# Motherboard.net
KiCad netlist of a schematic drawn in EAGLE
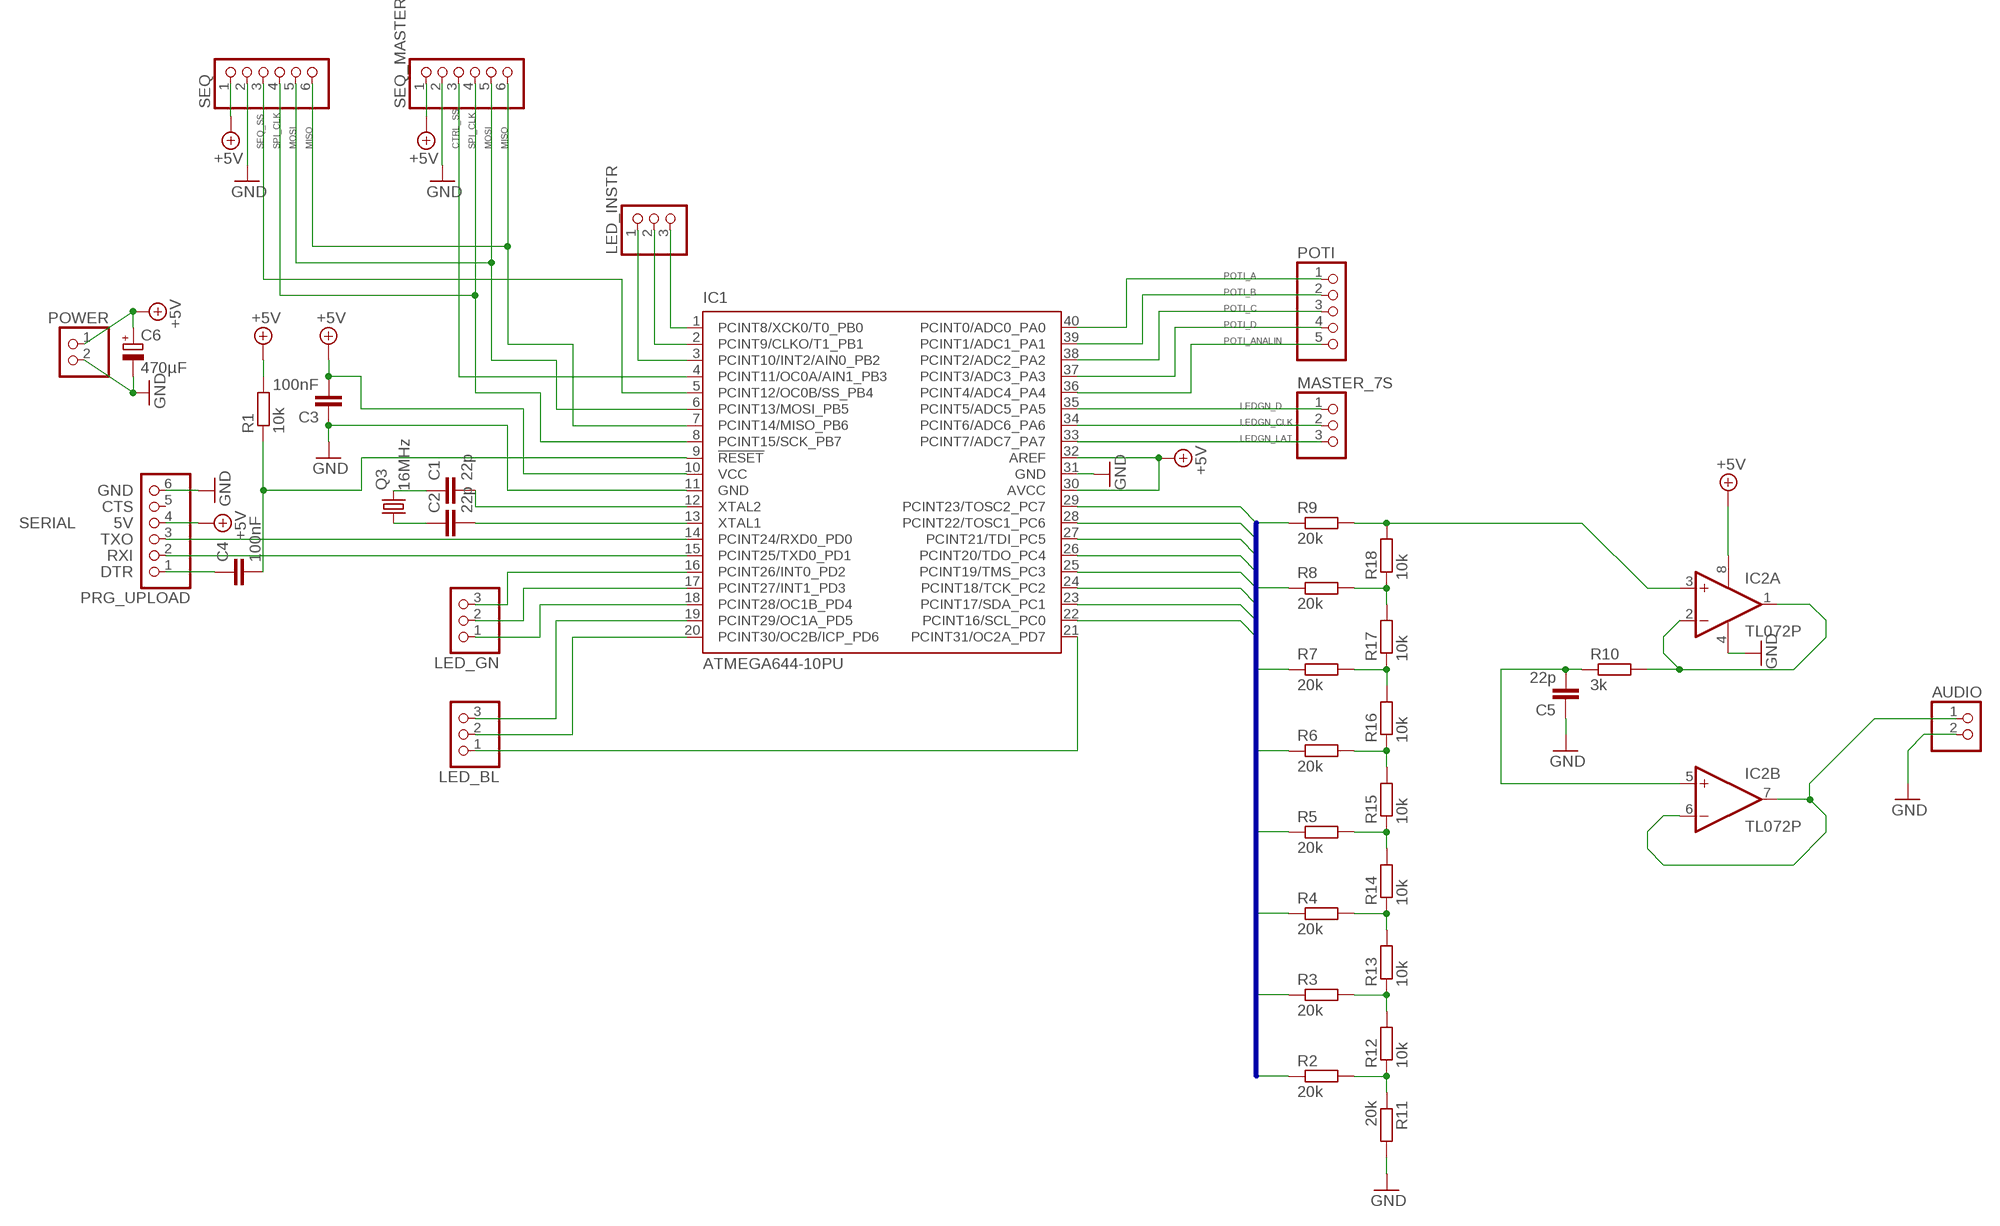
[diagram p0: schematic, sheet 1]

(export (version "E")
  (design (tool "Eeschema 10.0.6"))
  (components
    (comp (ref "AUDIO")
      (value "PINHD-1X2")
      (footprint "eagle-import:1X02")
      (libsource (lib "eagle-import") (part "PINHD-1X2"))
    )
    (comp (ref "C1")
      (value "22p")
      (footprint "eagle-import:C025-060X050")
      (libsource (lib "eagle-import") (part "C-EU025-060X050"))
    )
    (comp (ref "C2")
      (value "22p")
      (footprint "eagle-import:C025-060X050")
      (libsource (lib "eagle-import") (part "C-EU025-060X050"))
    )
    (comp (ref "C3")
      (value "100nF")
      (footprint "eagle-import:C025-060X050")
      (libsource (lib "eagle-import") (part "C-EU025-060X050"))
    )
    (comp (ref "C4")
      (value "100nF")
      (footprint "eagle-import:C025-060X050")
      (libsource (lib "eagle-import") (part "C-EU025-060X050"))
    )
    (comp (ref "C5")
      (value "22p")
      (footprint "eagle-import:C025-060X050")
      (libsource (lib "eagle-import") (part "C-EU025-060X050"))
    )
    (comp (ref "C6")
      (value "470µF")
      (footprint "eagle-import:E3,5-10")
      (libsource (lib "eagle-import") (part "CPOL-EUE3.5-10"))
    )
    (comp (ref "IC1")
      (value "ATMEGA644-10PU")
      (footprint "eagle-import:DIL40")
      (fields (field (name "MPN") "ATMEGA644V-10PU"))
      (libsource (lib "eagle-import") (part "ATMEGA644-PU10"))
    )
    (comp (ref "IC2")
      (value "TL072P")
      (footprint "eagle-import:DIL08")
      (libsource (lib "eagle-import") (part "TL072P"))
    )
    (comp (ref "LED_BL")
      (value "PINHD-1X3")
      (footprint "eagle-import:1X03")
      (libsource (lib "eagle-import") (part "PINHD-1X3"))
    )
    (comp (ref "LED_GN")
      (value "PINHD-1X3")
      (footprint "eagle-import:1X03")
      (libsource (lib "eagle-import") (part "PINHD-1X3"))
    )
    (comp (ref "LED_INSTR")
      (value "PINHD-1X3")
      (footprint "eagle-import:1X03")
      (libsource (lib "eagle-import") (part "PINHD-1X3"))
    )
    (comp (ref "MASTER_7S")
      (value "PINHD-1X3")
      (footprint "eagle-import:1X03")
      (libsource (lib "eagle-import") (part "PINHD-1X3"))
    )
    (comp (ref "POTI")
      (value "PINHD-1X5")
      (footprint "eagle-import:1X05")
      (libsource (lib "eagle-import") (part "PINHD-1X5"))
    )
    (comp (ref "POWER")
      (value "PINHD-1X2")
      (footprint "eagle-import:1X02")
      (libsource (lib "eagle-import") (part "PINHD-1X2"))
    )
    (comp (ref "PRG_UPLOAD")
      (value "PINHD-1X6")
      (footprint "eagle-import:1X06")
      (libsource (lib "eagle-import") (part "PINHD-1X6"))
    )
    (comp (ref "Q3")
      (value "16MHz")
      (footprint "eagle-import:HC18U-V")
      (libsource (lib "eagle-import") (part "CRYSTALHC18U-V"))
    )
    (comp (ref "R1")
      (value "10k")
      (footprint "eagle-import:0204_7")
      (libsource (lib "eagle-import") (part "R-EU_0204/7"))
    )
    (comp (ref "R2")
      (value "20k")
      (footprint "eagle-import:0204_7")
      (libsource (lib "eagle-import") (part "R-EU_0204/7"))
    )
    (comp (ref "R3")
      (value "20k")
      (footprint "eagle-import:0204_7")
      (libsource (lib "eagle-import") (part "R-EU_0204/7"))
    )
    (comp (ref "R4")
      (value "20k")
      (footprint "eagle-import:0204_7")
      (libsource (lib "eagle-import") (part "R-EU_0204/7"))
    )
    (comp (ref "R5")
      (value "20k")
      (footprint "eagle-import:0204_7")
      (libsource (lib "eagle-import") (part "R-EU_0204/7"))
    )
    (comp (ref "R6")
      (value "20k")
      (footprint "eagle-import:0204_7")
      (libsource (lib "eagle-import") (part "R-EU_0204/7"))
    )
    (comp (ref "R7")
      (value "20k")
      (footprint "eagle-import:0204_7")
      (libsource (lib "eagle-import") (part "R-EU_0204/7"))
    )
    (comp (ref "R8")
      (value "20k")
      (footprint "eagle-import:0204_7")
      (libsource (lib "eagle-import") (part "R-EU_0204/7"))
    )
    (comp (ref "R9")
      (value "20k")
      (footprint "eagle-import:0204_7")
      (libsource (lib "eagle-import") (part "R-EU_0204/7"))
    )
    (comp (ref "R10")
      (value "3k")
      (footprint "eagle-import:0204_7")
      (libsource (lib "eagle-import") (part "R-EU_0204/7"))
    )
    (comp (ref "R11")
      (value "20k")
      (footprint "eagle-import:0204_7")
      (libsource (lib "eagle-import") (part "R-EU_0204/7"))
    )
    (comp (ref "R12")
      (value "10k")
      (footprint "eagle-import:0204_7")
      (libsource (lib "eagle-import") (part "R-EU_0204/7"))
    )
    (comp (ref "R13")
      (value "10k")
      (footprint "eagle-import:0204_7")
      (libsource (lib "eagle-import") (part "R-EU_0204/7"))
    )
    (comp (ref "R14")
      (value "10k")
      (footprint "eagle-import:0204_7")
      (libsource (lib "eagle-import") (part "R-EU_0204/7"))
    )
    (comp (ref "R15")
      (value "10k")
      (footprint "eagle-import:0204_7")
      (libsource (lib "eagle-import") (part "R-EU_0204/7"))
    )
    (comp (ref "R16")
      (value "10k")
      (footprint "eagle-import:0204_7")
      (libsource (lib "eagle-import") (part "R-EU_0204/7"))
    )
    (comp (ref "R17")
      (value "10k")
      (footprint "eagle-import:0204_7")
      (libsource (lib "eagle-import") (part "R-EU_0204/7"))
    )
    (comp (ref "R18")
      (value "10k")
      (footprint "eagle-import:0204_7")
      (libsource (lib "eagle-import") (part "R-EU_0204/7"))
    )
    (comp (ref "SEQ")
      (value "PINHD-1X6")
      (footprint "eagle-import:1X06")
      (libsource (lib "eagle-import") (part "PINHD-1X6"))
    )
    (comp (ref "SEQ_MASTER")
      (value "PINHD-1X6")
      (footprint "eagle-import:1X06")
      (libsource (lib "eagle-import") (part "PINHD-1X6"))
    )
  )
  (nets
    (net (code "1") (name "+5V") (class "Default")
      (node (ref "C3") (pin "2") (pinfunction "2_2") (pintype "passive"))
      (node (ref "C6") (pin "+") (pinfunction "+_+") (pintype "passive"))
      (node (ref "IC1") (pin "10") (pinfunction "VCC_10") (pintype "power_in"))
      (node (ref "IC1") (pin "30") (pinfunction "AVCC_30") (pintype "power_in"))
      (node (ref "IC1") (pin "32") (pinfunction "AREF_32") (pintype "passive"))
      (node (ref "IC2") (pin "8") (pinfunction "V+_8") (pintype "power_in"))
      (node (ref "POWER") (pin "1") (pinfunction "1_1") (pintype "passive"))
      (node (ref "PRG_UPLOAD") (pin "4") (pinfunction "4_4") (pintype "passive"))
      (node (ref "R1") (pin "2") (pinfunction "2_2") (pintype "passive"))
      (node (ref "SEQ") (pin "1") (pinfunction "1_1") (pintype "passive"))
      (node (ref "SEQ_MASTER") (pin "1") (pinfunction "1_1") (pintype "passive"))
    )
    (net (code "2") (name "/CTRL_SS") (class "Default")
      (node (ref "IC1") (pin "4") (pinfunction "PCINT11/OC0A/AIN1_PB3_4") (pintype "bidirectional"))
      (node (ref "SEQ_MASTER") (pin "3") (pinfunction "3_3") (pintype "passive"))
    )
    (net (code "3") (name "/DA0") (class "Default")
      (node (ref "IC1") (pin "22") (pinfunction "PCINT16/SCL_PC0_22") (pintype "bidirectional"))
      (node (ref "R2") (pin "1") (pinfunction "1_1") (pintype "passive"))
    )
    (net (code "4") (name "/DA1") (class "Default")
      (node (ref "IC1") (pin "23") (pinfunction "PCINT17/SDA_PC1_23") (pintype "bidirectional"))
      (node (ref "R3") (pin "1") (pinfunction "1_1") (pintype "passive"))
    )
    (net (code "5") (name "/DA2") (class "Default")
      (node (ref "IC1") (pin "24") (pinfunction "PCINT18/TCK_PC2_24") (pintype "bidirectional"))
      (node (ref "R4") (pin "1") (pinfunction "1_1") (pintype "passive"))
    )
    (net (code "6") (name "/DA3") (class "Default")
      (node (ref "IC1") (pin "25") (pinfunction "PCINT19/TMS_PC3_25") (pintype "bidirectional"))
      (node (ref "R5") (pin "1") (pinfunction "1_1") (pintype "passive"))
    )
    (net (code "7") (name "/DA4") (class "Default")
      (node (ref "IC1") (pin "26") (pinfunction "PCINT20/TDO_PC4_26") (pintype "bidirectional"))
      (node (ref "R6") (pin "1") (pinfunction "1_1") (pintype "passive"))
    )
    (net (code "8") (name "/DA5") (class "Default")
      (node (ref "IC1") (pin "27") (pinfunction "PCINT21/TDI_PC5_27") (pintype "bidirectional"))
      (node (ref "R7") (pin "1") (pinfunction "1_1") (pintype "passive"))
    )
    (net (code "9") (name "/DA6") (class "Default")
      (node (ref "IC1") (pin "28") (pinfunction "PCINT22/TOSC1_PC6_28") (pintype "bidirectional"))
      (node (ref "R8") (pin "1") (pinfunction "1_1") (pintype "passive"))
    )
    (net (code "10") (name "/DA7") (class "Default")
      (node (ref "IC1") (pin "29") (pinfunction "PCINT23/TOSC2_PC7_29") (pintype "bidirectional"))
      (node (ref "R9") (pin "1") (pinfunction "1_1") (pintype "passive"))
    )
    (net (code "11") (name "/LEDGN_CLK") (class "Default")
      (node (ref "IC1") (pin "34") (pinfunction "PCINT6/ADC6_PA6_34") (pintype "bidirectional"))
      (node (ref "MASTER_7S") (pin "2") (pinfunction "2_2") (pintype "passive"))
    )
    (net (code "12") (name "/LEDGN_D") (class "Default")
      (node (ref "IC1") (pin "35") (pinfunction "PCINT5/ADC5_PA5_35") (pintype "bidirectional"))
      (node (ref "MASTER_7S") (pin "1") (pinfunction "1_1") (pintype "passive"))
    )
    (net (code "13") (name "/LEDGN_LAT") (class "Default")
      (node (ref "IC1") (pin "33") (pinfunction "PCINT7/ADC7_PA7_33") (pintype "bidirectional"))
      (node (ref "MASTER_7S") (pin "3") (pinfunction "3_3") (pintype "passive"))
    )
    (net (code "14") (name "/MISO") (class "Default")
      (node (ref "IC1") (pin "7") (pinfunction "PCINT14/MISO_PB6_7") (pintype "bidirectional"))
      (node (ref "SEQ") (pin "6") (pinfunction "6_6") (pintype "passive"))
      (node (ref "SEQ_MASTER") (pin "6") (pinfunction "6_6") (pintype "passive"))
    )
    (net (code "15") (name "/MOSI") (class "Default")
      (node (ref "IC1") (pin "6") (pinfunction "PCINT13/MOSI_PB5_6") (pintype "bidirectional"))
      (node (ref "SEQ") (pin "5") (pinfunction "5_5") (pintype "passive"))
      (node (ref "SEQ_MASTER") (pin "5") (pinfunction "5_5") (pintype "passive"))
    )
    (net (code "16") (name "/POTI_A") (class "Default")
      (node (ref "IC1") (pin "40") (pinfunction "PCINT0/ADC0_PA0_40") (pintype "bidirectional"))
      (node (ref "POTI") (pin "1") (pinfunction "1_1") (pintype "passive"))
    )
    (net (code "17") (name "/POTI_ANALIN") (class "Default")
      (node (ref "IC1") (pin "36") (pinfunction "PCINT4/ADC4_PA4_36") (pintype "bidirectional"))
      (node (ref "POTI") (pin "5") (pinfunction "5_5") (pintype "passive"))
    )
    (net (code "18") (name "/POTI_B") (class "Default")
      (node (ref "IC1") (pin "39") (pinfunction "PCINT1/ADC1_PA1_39") (pintype "bidirectional"))
      (node (ref "POTI") (pin "2") (pinfunction "2_2") (pintype "passive"))
    )
    (net (code "19") (name "/POTI_C") (class "Default")
      (node (ref "IC1") (pin "38") (pinfunction "PCINT2/ADC2_PA2_38") (pintype "bidirectional"))
      (node (ref "POTI") (pin "3") (pinfunction "3_3") (pintype "passive"))
    )
    (net (code "20") (name "/POTI_D") (class "Default")
      (node (ref "IC1") (pin "37") (pinfunction "PCINT3/ADC3_PA3_37") (pintype "bidirectional"))
      (node (ref "POTI") (pin "4") (pinfunction "4_4") (pintype "passive"))
    )
    (net (code "21") (name "/SEQ_SS") (class "Default")
      (node (ref "IC1") (pin "5") (pinfunction "PCINT12/OC0B/SS_PB4_5") (pintype "bidirectional"))
      (node (ref "SEQ") (pin "3") (pinfunction "3_3") (pintype "passive"))
    )
    (net (code "22") (name "/SPI_CLK") (class "Default")
      (node (ref "IC1") (pin "8") (pinfunction "PCINT15/SCK_PB7_8") (pintype "bidirectional"))
      (node (ref "SEQ") (pin "4") (pinfunction "4_4") (pintype "passive"))
      (node (ref "SEQ_MASTER") (pin "4") (pinfunction "4_4") (pintype "passive"))
    )
    (net (code "23") (name "GND") (class "Default")
      (node (ref "AUDIO") (pin "2") (pinfunction "2_2") (pintype "passive"))
      (node (ref "C3") (pin "1") (pinfunction "1_1") (pintype "passive"))
      (node (ref "C5") (pin "1") (pinfunction "1_1") (pintype "passive"))
      (node (ref "C6") (pin "-") (pinfunction "-_-") (pintype "passive"))
      (node (ref "IC1") (pin "11") (pinfunction "GND_11") (pintype "power_in"))
      (node (ref "IC1") (pin "31") (pinfunction "GND_31") (pintype "power_in"))
      (node (ref "IC2") (pin "4") (pinfunction "V-_4") (pintype "power_in"))
      (node (ref "POWER") (pin "2") (pinfunction "2_2") (pintype "passive"))
      (node (ref "PRG_UPLOAD") (pin "6") (pinfunction "6_6") (pintype "passive"))
      (node (ref "R11") (pin "2") (pinfunction "2_2") (pintype "passive"))
      (node (ref "SEQ") (pin "2") (pinfunction "2_2") (pintype "passive"))
      (node (ref "SEQ_MASTER") (pin "2") (pinfunction "2_2") (pintype "passive"))
    )
    (net (code "24") (name "Net-(C1-Pad1)") (class "Default")
      (node (ref "C1") (pin "1") (pinfunction "1_1") (pintype "passive"))
      (node (ref "Q3") (pin "2") (pinfunction "2_2") (pintype "passive"))
    )
    (net (code "25") (name "Net-(C2-Pad1)") (class "Default")
      (node (ref "C2") (pin "1") (pinfunction "1_1") (pintype "passive"))
      (node (ref "Q3") (pin "1") (pinfunction "1_1") (pintype "passive"))
    )
    (net (code "26") (name "Net-(C4-Pad1)") (class "Default")
      (node (ref "C4") (pin "1") (pinfunction "1_1") (pintype "passive"))
      (node (ref "PRG_UPLOAD") (pin "1") (pinfunction "1_1") (pintype "passive"))
    )
    (net (code "27") (name "Net-(IC1-PCINT8{slash}XCK0{slash}T0_PB0)") (class "Default")
      (node (ref "IC1") (pin "1") (pinfunction "PCINT8/XCK0/T0_PB0_1") (pintype "bidirectional"))
      (node (ref "LED_INSTR") (pin "3") (pinfunction "3_3") (pintype "passive"))
    )
    (net (code "28") (name "Net-(IC1-PCINT9{slash}CLKO{slash}T1_PB1)") (class "Default")
      (node (ref "IC1") (pin "2") (pinfunction "PCINT9/CLKO/T1_PB1_2") (pintype "bidirectional"))
      (node (ref "LED_INSTR") (pin "2") (pinfunction "2_2") (pintype "passive"))
    )
    (net (code "29") (name "Net-(IC1-PCINT10{slash}INT2{slash}AIN0_PB2)") (class "Default")
      (node (ref "IC1") (pin "3") (pinfunction "PCINT10/INT2/AIN0_PB2_3") (pintype "bidirectional"))
      (node (ref "LED_INSTR") (pin "1") (pinfunction "1_1") (pintype "passive"))
    )
    (net (code "30") (name "Net-(IC1-PCINT24{slash}RXD0_PD0)") (class "Default")
      (node (ref "IC1") (pin "14") (pinfunction "PCINT24/RXD0_PD0_14") (pintype "bidirectional"))
      (node (ref "PRG_UPLOAD") (pin "3") (pinfunction "3_3") (pintype "passive"))
    )
    (net (code "31") (name "Net-(IC1-PCINT25{slash}TXD0_PD1)") (class "Default")
      (node (ref "IC1") (pin "15") (pinfunction "PCINT25/TXD0_PD1_15") (pintype "bidirectional"))
      (node (ref "PRG_UPLOAD") (pin "2") (pinfunction "2_2") (pintype "passive"))
    )
    (net (code "32") (name "Net-(IC1-PCINT26{slash}INT0_PD2)") (class "Default")
      (node (ref "IC1") (pin "16") (pinfunction "PCINT26/INT0_PD2_16") (pintype "bidirectional"))
      (node (ref "LED_GN") (pin "3") (pinfunction "3_3") (pintype "passive"))
    )
    (net (code "33") (name "Net-(IC1-PCINT27{slash}INT1_PD3)") (class "Default")
      (node (ref "IC1") (pin "17") (pinfunction "PCINT27/INT1_PD3_17") (pintype "bidirectional"))
      (node (ref "LED_GN") (pin "2") (pinfunction "2_2") (pintype "passive"))
    )
    (net (code "34") (name "Net-(IC1-PCINT28{slash}OC1B_PD4)") (class "Default")
      (node (ref "IC1") (pin "18") (pinfunction "PCINT28/OC1B_PD4_18") (pintype "bidirectional"))
      (node (ref "LED_GN") (pin "1") (pinfunction "1_1") (pintype "passive"))
    )
    (net (code "35") (name "Net-(IC1-PCINT29{slash}OC1A_PD5)") (class "Default")
      (node (ref "IC1") (pin "19") (pinfunction "PCINT29/OC1A_PD5_19") (pintype "bidirectional"))
      (node (ref "LED_BL") (pin "3") (pinfunction "3_3") (pintype "passive"))
    )
    (net (code "36") (name "Net-(IC1-PCINT30{slash}OC2B{slash}ICP_PD6)") (class "Default")
      (node (ref "IC1") (pin "20") (pinfunction "PCINT30/OC2B/ICP_PD6_20") (pintype "bidirectional"))
      (node (ref "LED_BL") (pin "2") (pinfunction "2_2") (pintype "passive"))
    )
    (net (code "37") (name "Net-(IC1-PCINT31{slash}OC2A_PD7)") (class "Default")
      (node (ref "IC1") (pin "21") (pinfunction "PCINT31/OC2A_PD7_21") (pintype "bidirectional"))
      (node (ref "LED_BL") (pin "1") (pinfunction "1_1") (pintype "passive"))
    )
    (net (code "38") (name "Net-(IC1-XTAL1)") (class "Default")
      (node (ref "C2") (pin "2") (pinfunction "2_2") (pintype "passive"))
      (node (ref "IC1") (pin "13") (pinfunction "XTAL1_13") (pintype "input"))
    )
    (net (code "39") (name "Net-(IC1-XTAL2)") (class "Default")
      (node (ref "C1") (pin "2") (pinfunction "2_2") (pintype "passive"))
      (node (ref "IC1") (pin "12") (pinfunction "XTAL2_12") (pintype "output"))
    )
    (net (code "40") (name "Net-(IC1-~{RESET})") (class "Default")
      (node (ref "C4") (pin "2") (pinfunction "2_2") (pintype "passive"))
      (node (ref "IC1") (pin "9") (pinfunction "~{RESET}_9") (pintype "input"))
      (node (ref "R1") (pin "1") (pinfunction "1_1") (pintype "passive"))
    )
    (net (code "41") (name "Net-(IC2A-+IN)") (class "Default")
      (node (ref "IC2") (pin "3") (pinfunction "+IN_3") (pintype "input"))
      (node (ref "R18") (pin "2") (pinfunction "2_2") (pintype "passive"))
      (node (ref "R9") (pin "2") (pinfunction "2_2") (pintype "passive"))
    )
    (net (code "42") (name "Net-(IC2A--IN)") (class "Default")
      (node (ref "IC2") (pin "1") (pinfunction "OUT_1") (pintype "output"))
      (node (ref "IC2") (pin "2") (pinfunction "-IN_2") (pintype "input"))
      (node (ref "R10") (pin "2") (pinfunction "2_2") (pintype "passive"))
    )
    (net (code "43") (name "Net-(IC2B-+IN)") (class "Default")
      (node (ref "C5") (pin "2") (pinfunction "2_2") (pintype "passive"))
      (node (ref "IC2") (pin "5") (pinfunction "+IN_5") (pintype "input"))
      (node (ref "R10") (pin "1") (pinfunction "1_1") (pintype "passive"))
    )
    (net (code "44") (name "Net-(IC2B--IN)") (class "Default")
      (node (ref "AUDIO") (pin "1") (pinfunction "1_1") (pintype "passive"))
      (node (ref "IC2") (pin "6") (pinfunction "-IN_6") (pintype "input"))
      (node (ref "IC2") (pin "7") (pinfunction "OUT_7") (pintype "output"))
    )
    (net (code "45") (name "Net-(R11-Pad1)") (class "Default")
      (node (ref "R11") (pin "1") (pinfunction "1_1") (pintype "passive"))
      (node (ref "R12") (pin "1") (pinfunction "1_1") (pintype "passive"))
      (node (ref "R2") (pin "2") (pinfunction "2_2") (pintype "passive"))
    )
    (net (code "46") (name "Net-(R12-Pad2)") (class "Default")
      (node (ref "R12") (pin "2") (pinfunction "2_2") (pintype "passive"))
      (node (ref "R13") (pin "1") (pinfunction "1_1") (pintype "passive"))
      (node (ref "R3") (pin "2") (pinfunction "2_2") (pintype "passive"))
    )
    (net (code "47") (name "Net-(R13-Pad2)") (class "Default")
      (node (ref "R13") (pin "2") (pinfunction "2_2") (pintype "passive"))
      (node (ref "R14") (pin "1") (pinfunction "1_1") (pintype "passive"))
      (node (ref "R4") (pin "2") (pinfunction "2_2") (pintype "passive"))
    )
    (net (code "48") (name "Net-(R14-Pad2)") (class "Default")
      (node (ref "R14") (pin "2") (pinfunction "2_2") (pintype "passive"))
      (node (ref "R15") (pin "1") (pinfunction "1_1") (pintype "passive"))
      (node (ref "R5") (pin "2") (pinfunction "2_2") (pintype "passive"))
    )
    (net (code "49") (name "Net-(R15-Pad2)") (class "Default")
      (node (ref "R15") (pin "2") (pinfunction "2_2") (pintype "passive"))
      (node (ref "R16") (pin "1") (pinfunction "1_1") (pintype "passive"))
      (node (ref "R6") (pin "2") (pinfunction "2_2") (pintype "passive"))
    )
    (net (code "50") (name "Net-(R16-Pad2)") (class "Default")
      (node (ref "R16") (pin "2") (pinfunction "2_2") (pintype "passive"))
      (node (ref "R17") (pin "1") (pinfunction "1_1") (pintype "passive"))
      (node (ref "R7") (pin "2") (pinfunction "2_2") (pintype "passive"))
    )
    (net (code "51") (name "Net-(R17-Pad2)") (class "Default")
      (node (ref "R17") (pin "2") (pinfunction "2_2") (pintype "passive"))
      (node (ref "R18") (pin "1") (pinfunction "1_1") (pintype "passive"))
      (node (ref "R8") (pin "2") (pinfunction "2_2") (pintype "passive"))
    )
    (net (code "52") (name "unconnected-(PRG_UPLOAD-Pad5)") (class "Default")
      (node (ref "PRG_UPLOAD") (pin "5") (pinfunction "5_5") (pintype "passive"))
    )
  )
)
